# PWM.net
KiCad netlist of a schematic drawn in EAGLE
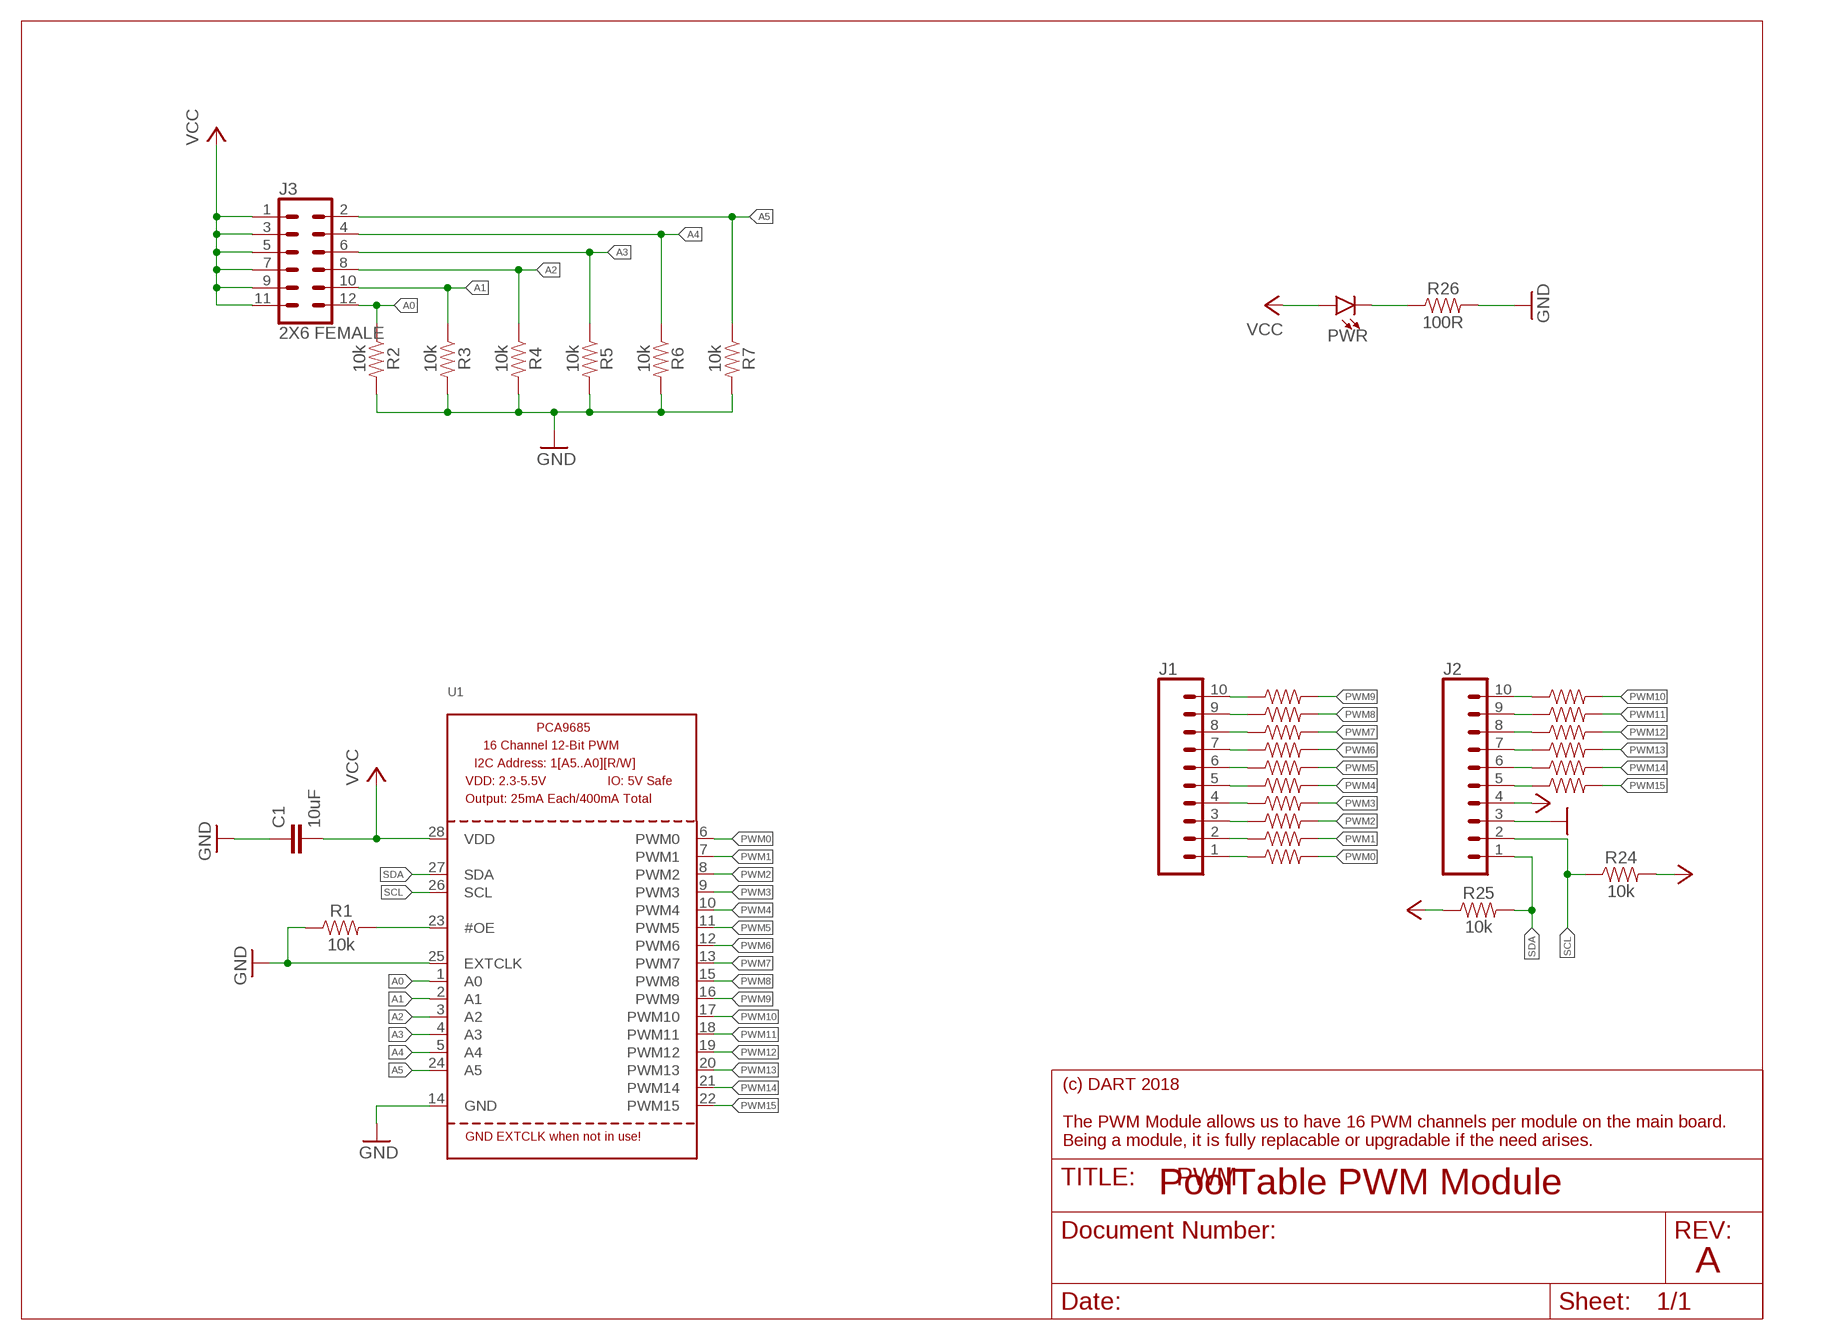
[diagram p0: schematic, sheet 1]

(export (version "E")
  (design (tool "Eeschema 10.0.6"))
  (components
    (comp (ref "C1")
      (value "10uF")
      (footprint "eagle-import:0603")
      (libsource (lib "eagle-import") (part "10UF-0603-6.3V-20%"))
    )
    (comp (ref "J1")
      (value "CONN_10\"")
      (footprint "eagle-import:1X10")
      (libsource (lib "eagle-import") (part "CONN_10{dblquote}"))
    )
    (comp (ref "J2")
      (value "CONN_10\"")
      (footprint "eagle-import:1X10")
      (libsource (lib "eagle-import") (part "CONN_10{dblquote}"))
    )
    (comp (ref "J3")
      (value "2X6 FEMALE")
      (footprint "eagle-import:2X6")
      (libsource (lib "eagle-import") (part "CONN_06X2PTH_FEMALE"))
    )
    (comp (ref "PWR")
      (value "LED0603")
      (footprint "eagle-import:LED-0603")
      (libsource (lib "eagle-import") (part "LED0603"))
    )
    (comp (ref "R1")
      (value "10k")
      (footprint "eagle-import:0603")
      (libsource (lib "eagle-import") (part "10KOHM-0603-1/10W-1%"))
    )
    (comp (ref "R2")
      (value "10k")
      (footprint "eagle-import:0603")
      (libsource (lib "eagle-import") (part "10KOHM-0603-1/10W-1%"))
    )
    (comp (ref "R3")
      (value "10k")
      (footprint "eagle-import:0603")
      (libsource (lib "eagle-import") (part "10KOHM-0603-1/10W-1%"))
    )
    (comp (ref "R4")
      (value "10k")
      (footprint "eagle-import:0603")
      (libsource (lib "eagle-import") (part "10KOHM-0603-1/10W-1%"))
    )
    (comp (ref "R5")
      (value "10k")
      (footprint "eagle-import:0603")
      (libsource (lib "eagle-import") (part "10KOHM-0603-1/10W-1%"))
    )
    (comp (ref "R6")
      (value "10k")
      (footprint "eagle-import:0603")
      (libsource (lib "eagle-import") (part "10KOHM-0603-1/10W-1%"))
    )
    (comp (ref "R7")
      (value "10k")
      (footprint "eagle-import:0603")
      (libsource (lib "eagle-import") (part "10KOHM-0603-1/10W-1%"))
    )
    (comp (ref "R8")
      (value "220")
      (footprint "eagle-import:0603")
      (libsource (lib "eagle-import") (part "220OHM-0603-1/10W-1%"))
    )
    (comp (ref "R9")
      (value "220")
      (footprint "eagle-import:0603")
      (libsource (lib "eagle-import") (part "220OHM-0603-1/10W-1%"))
    )
    (comp (ref "R10")
      (value "220")
      (footprint "eagle-import:0603")
      (libsource (lib "eagle-import") (part "220OHM-0603-1/10W-1%"))
    )
    (comp (ref "R11")
      (value "220")
      (footprint "eagle-import:0603")
      (libsource (lib "eagle-import") (part "220OHM-0603-1/10W-1%"))
    )
    (comp (ref "R12")
      (value "220")
      (footprint "eagle-import:0603")
      (libsource (lib "eagle-import") (part "220OHM-0603-1/10W-1%"))
    )
    (comp (ref "R13")
      (value "220")
      (footprint "eagle-import:0603")
      (libsource (lib "eagle-import") (part "220OHM-0603-1/10W-1%"))
    )
    (comp (ref "R14")
      (value "220")
      (footprint "eagle-import:0603")
      (libsource (lib "eagle-import") (part "220OHM-0603-1/10W-1%"))
    )
    (comp (ref "R15")
      (value "220")
      (footprint "eagle-import:0603")
      (libsource (lib "eagle-import") (part "220OHM-0603-1/10W-1%"))
    )
    (comp (ref "R16")
      (value "220")
      (footprint "eagle-import:0603")
      (libsource (lib "eagle-import") (part "220OHM-0603-1/10W-1%"))
    )
    (comp (ref "R17")
      (value "220")
      (footprint "eagle-import:0603")
      (libsource (lib "eagle-import") (part "220OHM-0603-1/10W-1%"))
    )
    (comp (ref "R18")
      (value "220")
      (footprint "eagle-import:0603")
      (libsource (lib "eagle-import") (part "220OHM-0603-1/10W-1%"))
    )
    (comp (ref "R19")
      (value "220")
      (footprint "eagle-import:0603")
      (libsource (lib "eagle-import") (part "220OHM-0603-1/10W-1%"))
    )
    (comp (ref "R20")
      (value "220")
      (footprint "eagle-import:0603")
      (libsource (lib "eagle-import") (part "220OHM-0603-1/10W-1%"))
    )
    (comp (ref "R21")
      (value "220")
      (footprint "eagle-import:0603")
      (libsource (lib "eagle-import") (part "220OHM-0603-1/10W-1%"))
    )
    (comp (ref "R22")
      (value "220")
      (footprint "eagle-import:0603")
      (libsource (lib "eagle-import") (part "220OHM-0603-1/10W-1%"))
    )
    (comp (ref "R23")
      (value "220")
      (footprint "eagle-import:0603")
      (libsource (lib "eagle-import") (part "220OHM-0603-1/10W-1%"))
    )
    (comp (ref "R24")
      (value "10k")
      (footprint "eagle-import:0603")
      (libsource (lib "eagle-import") (part "10KOHM-0603-1/10W-1%"))
    )
    (comp (ref "R25")
      (value "10k")
      (footprint "eagle-import:0603")
      (libsource (lib "eagle-import") (part "10KOHM-0603-1/10W-1%"))
    )
    (comp (ref "R26")
      (value "100R")
      (footprint "eagle-import:0603")
      (libsource (lib "eagle-import") (part "470OHM-0603-1/10W-1%"))
    )
    (comp (ref "U1")
      (value "PCA9685")
      (footprint "eagle-import:TSSOP28")
      (libsource (lib "eagle-import") (part "PCA9685"))
    )
  )
  (nets
    (net (code "1") (name "A0") (class "Default")
      (node (ref "J3") (pin "12") (pinfunction "12_12") (pintype "passive"))
      (node (ref "R2") (pin "1") (pinfunction "1_1") (pintype "passive"))
      (node (ref "U1") (pin "1") (pinfunction "A0_1") (pintype "bidirectional"))
    )
    (net (code "2") (name "A1") (class "Default")
      (node (ref "J3") (pin "10") (pinfunction "10_10") (pintype "passive"))
      (node (ref "R3") (pin "1") (pinfunction "1_1") (pintype "passive"))
      (node (ref "U1") (pin "2") (pinfunction "A1_2") (pintype "bidirectional"))
    )
    (net (code "3") (name "A2") (class "Default")
      (node (ref "J3") (pin "8") (pinfunction "8_8") (pintype "passive"))
      (node (ref "R4") (pin "1") (pinfunction "1_1") (pintype "passive"))
      (node (ref "U1") (pin "3") (pinfunction "A2_3") (pintype "bidirectional"))
    )
    (net (code "4") (name "A3") (class "Default")
      (node (ref "J3") (pin "6") (pinfunction "6_6") (pintype "passive"))
      (node (ref "R5") (pin "1") (pinfunction "1_1") (pintype "passive"))
      (node (ref "U1") (pin "4") (pinfunction "A3_4") (pintype "bidirectional"))
    )
    (net (code "5") (name "A4") (class "Default")
      (node (ref "J3") (pin "4") (pinfunction "4_4") (pintype "passive"))
      (node (ref "R6") (pin "1") (pinfunction "1_1") (pintype "passive"))
      (node (ref "U1") (pin "5") (pinfunction "A4_5") (pintype "bidirectional"))
    )
    (net (code "6") (name "A5") (class "Default")
      (node (ref "J3") (pin "2") (pinfunction "2_2") (pintype "passive"))
      (node (ref "R7") (pin "1") (pinfunction "1_1") (pintype "passive"))
      (node (ref "U1") (pin "24") (pinfunction "A5_24") (pintype "bidirectional"))
    )
    (net (code "7") (name "GND") (class "Default")
      (node (ref "C1") (pin "1") (pinfunction "1_1") (pintype "passive"))
      (node (ref "J2") (pin "3") (pinfunction "3_3") (pintype "passive"))
      (node (ref "R1") (pin "1") (pinfunction "1_1") (pintype "passive"))
      (node (ref "R2") (pin "2") (pinfunction "2_2") (pintype "passive"))
      (node (ref "R26") (pin "2") (pinfunction "2_2") (pintype "passive"))
      (node (ref "R3") (pin "2") (pinfunction "2_2") (pintype "passive"))
      (node (ref "R4") (pin "2") (pinfunction "2_2") (pintype "passive"))
      (node (ref "R5") (pin "2") (pinfunction "2_2") (pintype "passive"))
      (node (ref "R6") (pin "2") (pinfunction "2_2") (pintype "passive"))
      (node (ref "R7") (pin "2") (pinfunction "2_2") (pintype "passive"))
      (node (ref "U1") (pin "14") (pinfunction "GND_14") (pintype "power_in"))
      (node (ref "U1") (pin "25") (pinfunction "EXTCLK_25") (pintype "input"))
    )
    (net (code "8") (name "Net-(J1-Pad1)") (class "Default")
      (node (ref "J1") (pin "1") (pinfunction "1_1") (pintype "passive"))
      (node (ref "R17") (pin "1") (pinfunction "1_1") (pintype "passive"))
    )
    (net (code "9") (name "Net-(J1-Pad2)") (class "Default")
      (node (ref "J1") (pin "2") (pinfunction "2_2") (pintype "passive"))
      (node (ref "R16") (pin "1") (pinfunction "1_1") (pintype "passive"))
    )
    (net (code "10") (name "Net-(J1-Pad3)") (class "Default")
      (node (ref "J1") (pin "3") (pinfunction "3_3") (pintype "passive"))
      (node (ref "R15") (pin "1") (pinfunction "1_1") (pintype "passive"))
    )
    (net (code "11") (name "Net-(J1-Pad4)") (class "Default")
      (node (ref "J1") (pin "4") (pinfunction "4_4") (pintype "passive"))
      (node (ref "R14") (pin "1") (pinfunction "1_1") (pintype "passive"))
    )
    (net (code "12") (name "Net-(J1-Pad5)") (class "Default")
      (node (ref "J1") (pin "5") (pinfunction "5_5") (pintype "passive"))
      (node (ref "R13") (pin "1") (pinfunction "1_1") (pintype "passive"))
    )
    (net (code "13") (name "Net-(J1-Pad6)") (class "Default")
      (node (ref "J1") (pin "6") (pinfunction "6_6") (pintype "passive"))
      (node (ref "R12") (pin "1") (pinfunction "1_1") (pintype "passive"))
    )
    (net (code "14") (name "Net-(J1-Pad7)") (class "Default")
      (node (ref "J1") (pin "7") (pinfunction "7_7") (pintype "passive"))
      (node (ref "R11") (pin "1") (pinfunction "1_1") (pintype "passive"))
    )
    (net (code "15") (name "Net-(J1-Pad8)") (class "Default")
      (node (ref "J1") (pin "8") (pinfunction "8_8") (pintype "passive"))
      (node (ref "R10") (pin "1") (pinfunction "1_1") (pintype "passive"))
    )
    (net (code "16") (name "Net-(J1-Pad9)") (class "Default")
      (node (ref "J1") (pin "9") (pinfunction "9_9") (pintype "passive"))
      (node (ref "R9") (pin "1") (pinfunction "1_1") (pintype "passive"))
    )
    (net (code "17") (name "Net-(J1-Pad10)") (class "Default")
      (node (ref "J1") (pin "10") (pinfunction "10_10") (pintype "passive"))
      (node (ref "R8") (pin "1") (pinfunction "1_1") (pintype "passive"))
    )
    (net (code "18") (name "Net-(J2-Pad5)") (class "Default")
      (node (ref "J2") (pin "5") (pinfunction "5_5") (pintype "passive"))
      (node (ref "R23") (pin "1") (pinfunction "1_1") (pintype "passive"))
    )
    (net (code "19") (name "Net-(J2-Pad6)") (class "Default")
      (node (ref "J2") (pin "6") (pinfunction "6_6") (pintype "passive"))
      (node (ref "R22") (pin "1") (pinfunction "1_1") (pintype "passive"))
    )
    (net (code "20") (name "Net-(J2-Pad7)") (class "Default")
      (node (ref "J2") (pin "7") (pinfunction "7_7") (pintype "passive"))
      (node (ref "R21") (pin "1") (pinfunction "1_1") (pintype "passive"))
    )
    (net (code "21") (name "Net-(J2-Pad8)") (class "Default")
      (node (ref "J2") (pin "8") (pinfunction "8_8") (pintype "passive"))
      (node (ref "R20") (pin "1") (pinfunction "1_1") (pintype "passive"))
    )
    (net (code "22") (name "Net-(J2-Pad9)") (class "Default")
      (node (ref "J2") (pin "9") (pinfunction "9_9") (pintype "passive"))
      (node (ref "R19") (pin "1") (pinfunction "1_1") (pintype "passive"))
    )
    (net (code "23") (name "Net-(J2-Pad10)") (class "Default")
      (node (ref "J2") (pin "10") (pinfunction "10_10") (pintype "passive"))
      (node (ref "R18") (pin "1") (pinfunction "1_1") (pintype "passive"))
    )
    (net (code "24") (name "Net-(PWR-PadC)") (class "Default")
      (node (ref "PWR") (pin "C") (pinfunction "C_C") (pintype "passive"))
      (node (ref "R26") (pin "1") (pinfunction "1_1") (pintype "passive"))
    )
    (net (code "25") (name "Net-(U1-#OE)") (class "Default")
      (node (ref "R1") (pin "2") (pinfunction "2_2") (pintype "passive"))
      (node (ref "U1") (pin "23") (pinfunction "#OE_23") (pintype "input"))
    )
    (net (code "26") (name "PWM0") (class "Default")
      (node (ref "R17") (pin "2") (pinfunction "2_2") (pintype "passive"))
      (node (ref "U1") (pin "6") (pinfunction "PWM0_6") (pintype "output"))
    )
    (net (code "27") (name "PWM1") (class "Default")
      (node (ref "R16") (pin "2") (pinfunction "2_2") (pintype "passive"))
      (node (ref "U1") (pin "7") (pinfunction "PWM1_7") (pintype "output"))
    )
    (net (code "28") (name "PWM2") (class "Default")
      (node (ref "R15") (pin "2") (pinfunction "2_2") (pintype "passive"))
      (node (ref "U1") (pin "8") (pinfunction "PWM2_8") (pintype "output"))
    )
    (net (code "29") (name "PWM3") (class "Default")
      (node (ref "R14") (pin "2") (pinfunction "2_2") (pintype "passive"))
      (node (ref "U1") (pin "9") (pinfunction "PWM3_9") (pintype "output"))
    )
    (net (code "30") (name "PWM4") (class "Default")
      (node (ref "R13") (pin "2") (pinfunction "2_2") (pintype "passive"))
      (node (ref "U1") (pin "10") (pinfunction "PWM4_10") (pintype "output"))
    )
    (net (code "31") (name "PWM5") (class "Default")
      (node (ref "R12") (pin "2") (pinfunction "2_2") (pintype "passive"))
      (node (ref "U1") (pin "11") (pinfunction "PWM5_11") (pintype "output"))
    )
    (net (code "32") (name "PWM6") (class "Default")
      (node (ref "R11") (pin "2") (pinfunction "2_2") (pintype "passive"))
      (node (ref "U1") (pin "12") (pinfunction "PWM6_12") (pintype "output"))
    )
    (net (code "33") (name "PWM7") (class "Default")
      (node (ref "R10") (pin "2") (pinfunction "2_2") (pintype "passive"))
      (node (ref "U1") (pin "13") (pinfunction "PWM7_13") (pintype "output"))
    )
    (net (code "34") (name "PWM8") (class "Default")
      (node (ref "R9") (pin "2") (pinfunction "2_2") (pintype "passive"))
      (node (ref "U1") (pin "15") (pinfunction "PWM8_15") (pintype "output"))
    )
    (net (code "35") (name "PWM9") (class "Default")
      (node (ref "R8") (pin "2") (pinfunction "2_2") (pintype "passive"))
      (node (ref "U1") (pin "16") (pinfunction "PWM9_16") (pintype "output"))
    )
    (net (code "36") (name "PWM10") (class "Default")
      (node (ref "R18") (pin "2") (pinfunction "2_2") (pintype "passive"))
      (node (ref "U1") (pin "17") (pinfunction "PWM10_17") (pintype "output"))
    )
    (net (code "37") (name "PWM11") (class "Default")
      (node (ref "R19") (pin "2") (pinfunction "2_2") (pintype "passive"))
      (node (ref "U1") (pin "18") (pinfunction "PWM11_18") (pintype "output"))
    )
    (net (code "38") (name "PWM12") (class "Default")
      (node (ref "R20") (pin "2") (pinfunction "2_2") (pintype "passive"))
      (node (ref "U1") (pin "19") (pinfunction "PWM12_19") (pintype "output"))
    )
    (net (code "39") (name "PWM13") (class "Default")
      (node (ref "R21") (pin "2") (pinfunction "2_2") (pintype "passive"))
      (node (ref "U1") (pin "20") (pinfunction "PWM13_20") (pintype "output"))
    )
    (net (code "40") (name "PWM14") (class "Default")
      (node (ref "R22") (pin "2") (pinfunction "2_2") (pintype "passive"))
      (node (ref "U1") (pin "21") (pinfunction "PWM14_21") (pintype "output"))
    )
    (net (code "41") (name "PWM15") (class "Default")
      (node (ref "R23") (pin "2") (pinfunction "2_2") (pintype "passive"))
      (node (ref "U1") (pin "22") (pinfunction "PWM15_22") (pintype "output"))
    )
    (net (code "42") (name "SCL") (class "Default")
      (node (ref "J2") (pin "2") (pinfunction "2_2") (pintype "passive"))
      (node (ref "R24") (pin "1") (pinfunction "1_1") (pintype "passive"))
      (node (ref "U1") (pin "26") (pinfunction "SCL_26") (pintype "bidirectional"))
    )
    (net (code "43") (name "SDA") (class "Default")
      (node (ref "J2") (pin "1") (pinfunction "1_1") (pintype "passive"))
      (node (ref "R25") (pin "2") (pinfunction "2_2") (pintype "passive"))
      (node (ref "U1") (pin "27") (pinfunction "SDA_27") (pintype "bidirectional"))
    )
    (net (code "44") (name "VCC") (class "Default")
      (node (ref "C1") (pin "2") (pinfunction "2_2") (pintype "passive"))
      (node (ref "J2") (pin "4") (pinfunction "4_4") (pintype "passive"))
      (node (ref "J3") (pin "1") (pinfunction "1_1") (pintype "passive"))
      (node (ref "J3") (pin "11") (pinfunction "11_11") (pintype "passive"))
      (node (ref "J3") (pin "3") (pinfunction "3_3") (pintype "passive"))
      (node (ref "J3") (pin "5") (pinfunction "5_5") (pintype "passive"))
      (node (ref "J3") (pin "7") (pinfunction "7_7") (pintype "passive"))
      (node (ref "J3") (pin "9") (pinfunction "9_9") (pintype "passive"))
      (node (ref "PWR") (pin "A") (pinfunction "A_A") (pintype "passive"))
      (node (ref "R24") (pin "2") (pinfunction "2_2") (pintype "passive"))
      (node (ref "R25") (pin "1") (pinfunction "1_1") (pintype "passive"))
      (node (ref "U1") (pin "28") (pinfunction "VDD_28") (pintype "power_in"))
    )
  )
)
